# pipowerrealy.net
KiCad netlist of a schematic drawn in EAGLE
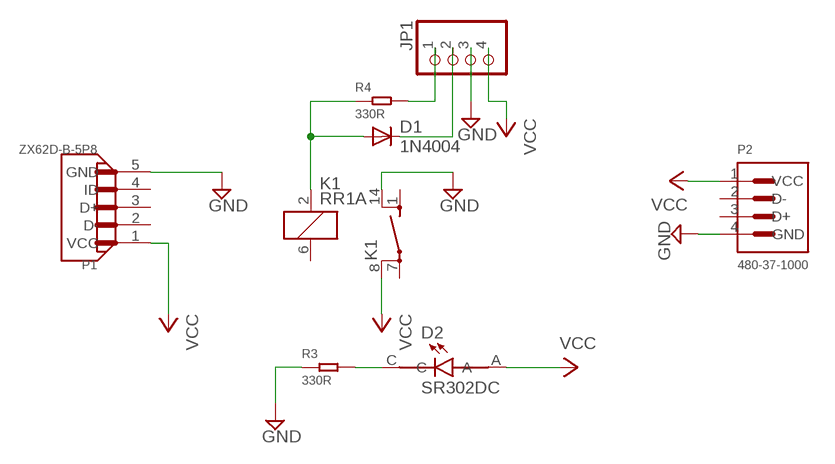
[diagram p0: schematic, sheet 1]

(export (version "E")
  (design (tool "Eeschema 10.0.6"))
  (components
    (comp (ref "D1")
      (value "1N4004")
      (footprint "eagle-import:DO41-10")
      (libsource (lib "eagle-import") (part "1N4004"))
    )
    (comp (ref "D2")
      (value "SR302DC")
      (footprint "eagle-import:LED_SR302DC")
      (fields (field (name "MANUFACTURER") "Chengguangxing"))
      (libsource (lib "eagle-import") (part "SR302DC"))
    )
    (comp (ref "JP1")
      (value "PINHD-1X4")
      (footprint "eagle-import:1X04")
      (libsource (lib "eagle-import") (part "PINHD-1X4"))
    )
    (comp (ref "K1")
      (value "RR1A")
      (footprint "eagle-import:RR1A")
      (libsource (lib "eagle-import") (part "RR1A"))
    )
    (comp (ref "P1")
      (value "ZX62D-B-5P8")
      (footprint "eagle-import:HRS_ZX62D-B-5P8")
      (fields (field (name "MANUFACTURER") "Hirose"))
      (libsource (lib "eagle-import") (part "ZX62D-B-5P8"))
    )
    (comp (ref "P2")
      (value "480-37-1000")
      (footprint "eagle-import:MOLEX_480-37-1000")
      (fields (field (name "MANUFACTURER") "Molex"))
      (libsource (lib "eagle-import") (part "480-37-1000"))
    )
    (comp (ref "R3")
      (value "330R")
      (footprint "eagle-import:PR-D2.3XL6.5MM")
      (fields (field (name "MPN") "FHCFR-1/4W-331J"))
      (libsource (lib "eagle-import") (part "DIP-RES-330R-5%-1/4W(PR-D2.3XL6.5MM)"))
    )
    (comp (ref "R4")
      (value "330R")
      (footprint "eagle-import:PR-D2.3XL6.5MM")
      (fields (field (name "MPN") "FHCFR-1/4W-331J"))
      (libsource (lib "eagle-import") (part "DIP-RES-330R-5%-1/4W(PR-D2.3XL6.5MM)"))
    )
  )
  (nets
    (net (code "1") (name "GND") (class "Default")
      (node (ref "JP1") (pin "3") (pinfunction "3_3") (pintype "passive"))
      (node (ref "K1") (pin "14") (pinfunction "S_14") (pintype "passive"))
      (node (ref "P1") (pin "5") (pinfunction "GND_5") (pintype "power_in"))
      (node (ref "P2") (pin "4") (pinfunction "GND_4") (pintype "power_in"))
      (node (ref "R3") (pin "1") (pinfunction "1_1") (pintype "passive"))
    )
    (net (code "2") (name "Net-(D1-PadC)") (class "Default")
      (node (ref "D1") (pin "C") (pinfunction "C_C") (pintype "passive"))
      (node (ref "JP1") (pin "2") (pinfunction "2_2") (pintype "passive"))
    )
    (net (code "3") (name "Net-(D2-PadC)") (class "Default")
      (node (ref "D2") (pin "C") (pinfunction "C_C") (pintype "passive"))
      (node (ref "R3") (pin "2") (pinfunction "2_2") (pintype "passive"))
    )
    (net (code "4") (name "Net-(JP1-Pad1)") (class "Default")
      (node (ref "JP1") (pin "1") (pinfunction "1_1") (pintype "passive"))
      (node (ref "R4") (pin "2") (pinfunction "2_2") (pintype "passive"))
    )
    (net (code "5") (name "Net-(K1A-1)") (class "Default")
      (node (ref "D1") (pin "A") (pinfunction "A_A") (pintype "passive"))
      (node (ref "K1") (pin "2") (pinfunction "1_2") (pintype "passive"))
      (node (ref "R4") (pin "1") (pinfunction "1_1") (pintype "passive"))
    )
    (net (code "6") (name "VCC") (class "Default")
      (node (ref "D2") (pin "A") (pinfunction "A_A") (pintype "passive"))
      (node (ref "JP1") (pin "4") (pinfunction "4_4") (pintype "passive"))
      (node (ref "K1") (pin "8") (pinfunction "P_8") (pintype "passive"))
      (node (ref "P1") (pin "1") (pinfunction "VCC_1") (pintype "power_in"))
      (node (ref "P2") (pin "1") (pinfunction "VCC_1") (pintype "power_in"))
    )
    (net (code "7") (name "unconnected-(K1A-2-Pad6)") (class "Default")
      (node (ref "K1") (pin "6") (pinfunction "2_6") (pintype "passive"))
    )
    (net (code "8") (name "unconnected-(K1B-P-Pad7)") (class "Default")
      (node (ref "K1") (pin "7") (pinfunction "P_7") (pintype "passive"))
    )
    (net (code "9") (name "unconnected-(K1B-S-Pad1)") (class "Default")
      (node (ref "K1") (pin "1") (pinfunction "S_1") (pintype "passive"))
    )
    (net (code "10") (name "unconnected-(P1-D+-Pad3)") (class "Default")
      (node (ref "P1") (pin "3") (pinfunction "D+_3") (pintype "passive"))
    )
    (net (code "11") (name "unconnected-(P1-D--Pad2)") (class "Default")
      (node (ref "P1") (pin "2") (pinfunction "D-_2") (pintype "passive"))
    )
    (net (code "12") (name "unconnected-(P1-ID-Pad4)") (class "Default")
      (node (ref "P1") (pin "4") (pinfunction "ID_4") (pintype "passive"))
    )
    (net (code "13") (name "unconnected-(P2-D+-Pad3)") (class "Default")
      (node (ref "P2") (pin "3") (pinfunction "D+_3") (pintype "bidirectional"))
    )
    (net (code "14") (name "unconnected-(P2-D--Pad2)") (class "Default")
      (node (ref "P2") (pin "2") (pinfunction "D-_2") (pintype "bidirectional"))
    )
  )
)
